# top_overview.net
KiCad netlist of a schematic drawn in Altium Designer
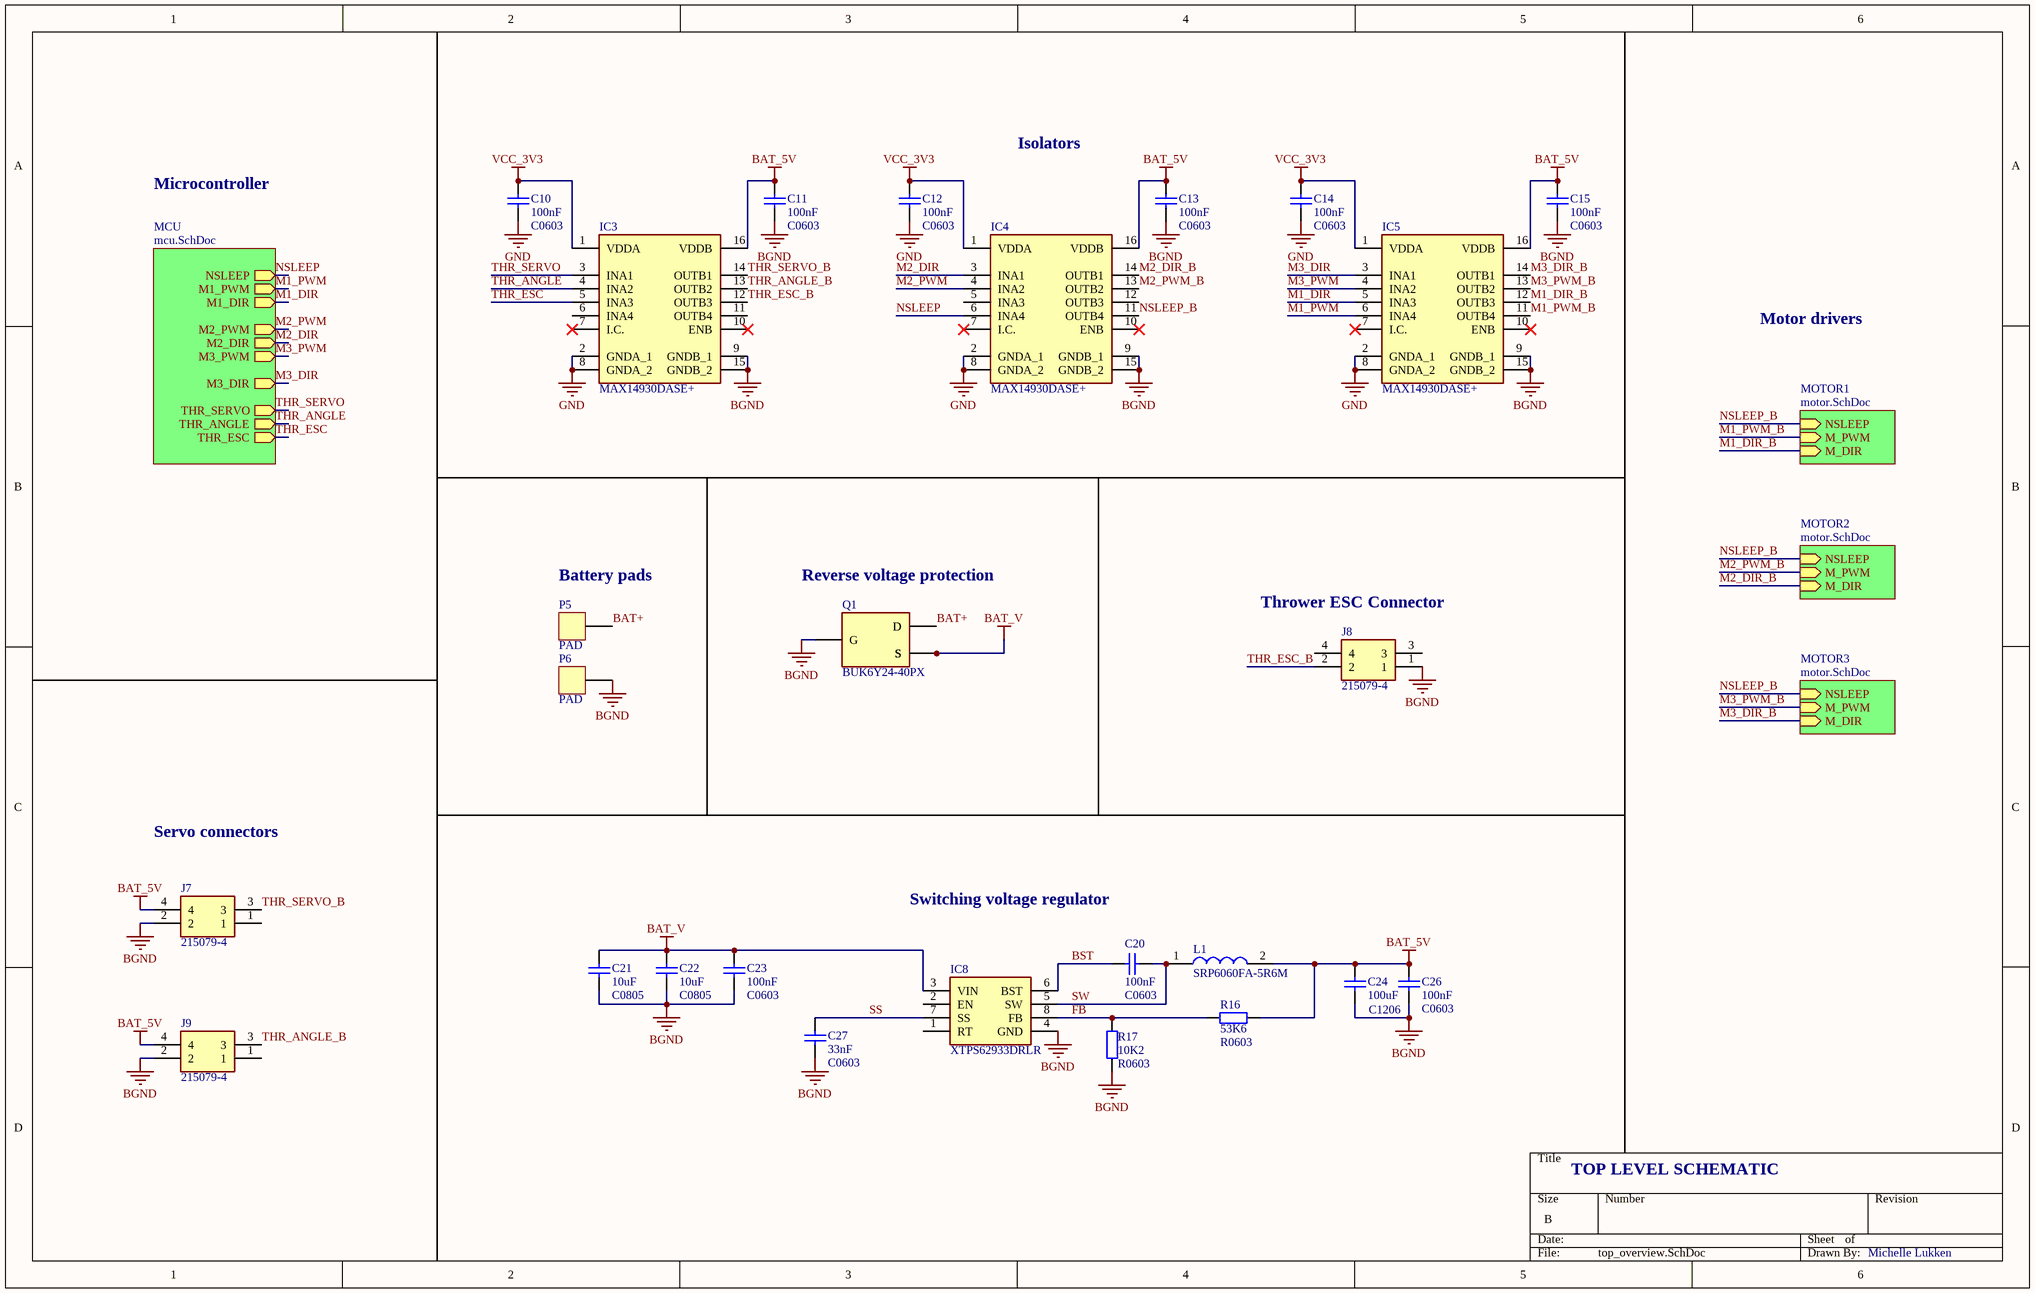
[diagram p0: top_overview.SchDoc]

(export (version "E")
  (design (tool "Eeschema 10.0.6"))
  (components
    (comp (ref "C10")
      (value "100nF*V")
      (footprint "PCB Passives:C0603")
      (description "Ceramic capacitor")
      (fields (field (name "CAPACITANCE") "100nF"))
      (libsource (lib "DeltaX_basketball_mikro") (part "Capacitor"))
    )
    (comp (ref "C11")
      (value "100nF*V")
      (footprint "PCB Passives:C0603")
      (description "Ceramic capacitor")
      (fields (field (name "CAPACITANCE") "100nF"))
      (libsource (lib "DeltaX_basketball_mikro") (part "Capacitor"))
    )
    (comp (ref "C12")
      (value "100nF*V")
      (footprint "PCB Passives:C0603")
      (description "Ceramic capacitor")
      (fields (field (name "CAPACITANCE") "100nF"))
      (libsource (lib "DeltaX_basketball_mikro") (part "Capacitor"))
    )
    (comp (ref "C13")
      (value "100nF*V")
      (footprint "PCB Passives:C0603")
      (description "Ceramic capacitor")
      (fields (field (name "CAPACITANCE") "100nF"))
      (libsource (lib "DeltaX_basketball_mikro") (part "Capacitor"))
    )
    (comp (ref "C14")
      (value "100nF*V")
      (footprint "PCB Passives:C0603")
      (description "Ceramic capacitor")
      (fields (field (name "CAPACITANCE") "100nF"))
      (libsource (lib "DeltaX_basketball_mikro") (part "Capacitor"))
    )
    (comp (ref "C15")
      (value "100nF*V")
      (footprint "PCB Passives:C0603")
      (description "Ceramic capacitor")
      (fields (field (name "CAPACITANCE") "100nF"))
      (libsource (lib "DeltaX_basketball_mikro") (part "Capacitor"))
    )
    (comp (ref "C20")
      (value "100nF*V")
      (footprint "PCB Passives:C0603")
      (description "Ceramic capacitor")
      (fields (field (name "CAPACITANCE") "100nF"))
      (libsource (lib "DeltaX_basketball_mikro") (part "Capacitor"))
    )
    (comp (ref "C21")
      (value "10uF*V")
      (footprint "C0805")
      (description "Ceramic capacitor")
      (fields (field (name "CAPACITANCE") "10uF"))
      (libsource (lib "DeltaX_basketball_mikro") (part "Capacitor"))
    )
    (comp (ref "C22")
      (value "10uF*V")
      (footprint "C0805")
      (description "Ceramic capacitor")
      (fields (field (name "CAPACITANCE") "10uF"))
      (libsource (lib "DeltaX_basketball_mikro") (part "Capacitor"))
    )
    (comp (ref "C23")
      (value "100nF*V")
      (footprint "PCB Passives:C0603")
      (description "Ceramic capacitor")
      (fields (field (name "CAPACITANCE") "100nF"))
      (libsource (lib "DeltaX_basketball_mikro") (part "Capacitor"))
    )
    (comp (ref "C24")
      (value "100uF*V")
      (footprint "C1206")
      (description "Ceramic capacitor")
      (fields (field (name "CAPACITANCE") "100uF"))
      (libsource (lib "DeltaX_basketball_mikro") (part "Capacitor"))
    )
    (comp (ref "C26")
      (value "100nF*V")
      (footprint "PCB Passives:C0603")
      (description "Ceramic capacitor")
      (fields (field (name "CAPACITANCE") "100nF"))
      (libsource (lib "DeltaX_basketball_mikro") (part "Capacitor"))
    )
    (comp (ref "C27")
      (value "33nF*V")
      (footprint "PCB Passives:C0603")
      (description "Ceramic capacitor")
      (fields (field (name "CAPACITANCE") "33nF"))
      (libsource (lib "DeltaX_basketball_mikro") (part "Capacitor"))
    )
    (comp (ref "IC3")
      (value "MAX14930DASE+")
      (footprint "SamacSys:SOIC127P600X175-16N")
      (description "Integrated Circuit")
      (fields
        (field (name "MANUFACTURER_PART_NUMBER") "MAX14930EASE+")
        (field (name "MOUSER PART NUMBER") "700-MAX14930EASE+")
      )
      (libsource (lib "DeltaX_basketball_mikro") (part "MAX14930DASE+"))
    )
    (comp (ref "IC4")
      (value "MAX14930DASE+")
      (footprint "SamacSys:SOIC127P600X175-16N")
      (description "Integrated Circuit")
      (fields
        (field (name "MANUFACTURER_PART_NUMBER") "MAX14930EASE+")
        (field (name "MOUSER PART NUMBER") "700-MAX14930EASE+")
      )
      (libsource (lib "DeltaX_basketball_mikro") (part "MAX14930DASE+"))
    )
    (comp (ref "IC5")
      (value "MAX14930DASE+")
      (footprint "SamacSys:SOIC127P600X175-16N")
      (description "Integrated Circuit")
      (fields
        (field (name "MANUFACTURER_PART_NUMBER") "MAX14930EASE+")
        (field (name "MOUSER PART NUMBER") "700-MAX14930EASE+")
      )
      (libsource (lib "DeltaX_basketball_mikro") (part "MAX14930DASE+"))
    )
    (comp (ref "IC8")
      (value "XTPS62933DRLR")
      (footprint "SamacSys:SOTFL50P160X60-8N")
      (description "Integrated Circuit")
      (fields
        (field (name "MANUFACTURER_PART_NUMBER") "TPS62933DRLR")
        (field (name "MOUSER PART NUMBER") "595-TPS62933DRLR")
      )
      (libsource (lib "DeltaX_basketball_mikro") (part "XTPS62933DRLR"))
    )
    (comp (ref "J7")
      (value "215079-4")
      (footprint "SamacSys:2150794")
      (description "Connector")
      (fields (field (name "MOUSER PART NUMBER") "571-215079-4"))
      (libsource (lib "DeltaX_basketball_mikro") (part "215079-4"))
    )
    (comp (ref "J8")
      (value "215079-4")
      (footprint "SamacSys:2150794")
      (description "Connector")
      (fields (field (name "MOUSER PART NUMBER") "571-215079-4"))
      (libsource (lib "DeltaX_basketball_mikro") (part "215079-4"))
    )
    (comp (ref "J9")
      (value "215079-4")
      (footprint "SamacSys:2150794")
      (description "Connector")
      (fields (field (name "MOUSER PART NUMBER") "571-215079-4"))
      (libsource (lib "DeltaX_basketball_mikro") (part "215079-4"))
    )
    (comp (ref "L1")
      (value "SRP6060FA-5R6M")
      (footprint "SamacSys:SRP6060FA5R6M")
      (description "Inductor")
      (fields (field (name "MOUSER PART NUMBER") "652-SRP6060FA-5R6M"))
      (libsource (lib "*") (part "SRP6060FA-5R6M"))
    )
    (comp (ref "P5") (value "PAD") (footprint "SamacSys:BIG_PAD") (libsource (lib "SamacSys") (part "PAD")))
    (comp (ref "P6") (value "PAD") (footprint "SamacSys:BIG_PAD") (libsource (lib "SamacSys") (part "PAD")))
    (comp (ref "Q1")
      (value "BUK6Y24-40PX")
      (footprint "SamacSys:BUK6Y2440PX")
      (description "MOSFET (P-Channel)")
      (fields (field (name "MOUSER PART NUMBER") "771-BUK6Y24-40PX"))
      (libsource (lib "DeltaX_basketball_mikro") (part "BUK6Y24-40PX"))
    )
    (comp (ref "R16")
      (value "53K6")
      (footprint "R0603")
      (description "Resistor")
      (fields (field (name "RESISTANCE") "53K6"))
      (libsource (lib "Component Library INTLIB") (part "Resistor"))
    )
    (comp (ref "R17")
      (value "10K2")
      (footprint "R0603")
      (description "Resistor")
      (fields (field (name "RESISTANCE") "10K2"))
      (libsource (lib "") (part "Resistor_1"))
    )
  )
  (nets
    (net (code "1") (name "/BAT+") (class "Default")
      (node (ref "P5") (pin "1") (pinfunction "PAD_1") (pintype "passive"))
      (node (ref "Q1") (pin "5") (pinfunction "D_5") (pintype "passive"))
      (node (ref "Q1") (pin "6") (pinfunction "D_6") (pintype "passive"))
    )
    (net (code "2") (name "/BST") (class "Default")
      (node (ref "C20") (pin "2") (pinfunction "2_2") (pintype "passive"))
      (node (ref "IC8") (pin "6") (pinfunction "BST_6") (pintype "passive"))
    )
    (net (code "3") (name "/FB") (class "Default")
      (node (ref "IC8") (pin "8") (pinfunction "FB_8") (pintype "passive"))
      (node (ref "R16") (pin "1") (pinfunction "1_1") (pintype "passive"))
      (node (ref "R17") (pin "1") (pinfunction "1_1") (pintype "passive"))
    )
    (net (code "4") (name "/M1_DIR") (class "Default")
      (node (ref "IC5") (pin "5") (pinfunction "INA3_5") (pintype "passive"))
    )
    (net (code "5") (name "/M1_DIR_B") (class "Default")
      (node (ref "IC5") (pin "12") (pinfunction "OUTB3_12") (pintype "passive"))
    )
    (net (code "6") (name "/M1_PWM") (class "Default")
      (node (ref "IC5") (pin "6") (pinfunction "INA4_6") (pintype "passive"))
    )
    (net (code "7") (name "/M1_PWM_B") (class "Default")
      (node (ref "IC5") (pin "11") (pinfunction "OUTB4_11") (pintype "passive"))
    )
    (net (code "8") (name "/M2_DIR") (class "Default")
      (node (ref "IC4") (pin "3") (pinfunction "INA1_3") (pintype "passive"))
    )
    (net (code "9") (name "/M2_DIR_B") (class "Default")
      (node (ref "IC4") (pin "14") (pinfunction "OUTB1_14") (pintype "passive"))
    )
    (net (code "10") (name "/M2_PWM") (class "Default")
      (node (ref "IC4") (pin "4") (pinfunction "INA2_4") (pintype "passive"))
    )
    (net (code "11") (name "/M2_PWM_B") (class "Default")
      (node (ref "IC4") (pin "13") (pinfunction "OUTB2_13") (pintype "passive"))
    )
    (net (code "12") (name "/M3_DIR") (class "Default")
      (node (ref "IC5") (pin "3") (pinfunction "INA1_3") (pintype "passive"))
    )
    (net (code "13") (name "/M3_DIR_B") (class "Default")
      (node (ref "IC5") (pin "14") (pinfunction "OUTB1_14") (pintype "passive"))
    )
    (net (code "14") (name "/M3_PWM") (class "Default")
      (node (ref "IC5") (pin "4") (pinfunction "INA2_4") (pintype "passive"))
    )
    (net (code "15") (name "/M3_PWM_B") (class "Default")
      (node (ref "IC5") (pin "13") (pinfunction "OUTB2_13") (pintype "passive"))
    )
    (net (code "16") (name "/NSLEEP") (class "Default")
      (node (ref "IC4") (pin "6") (pinfunction "INA4_6") (pintype "passive"))
    )
    (net (code "17") (name "/NSLEEP_B") (class "Default")
      (node (ref "IC4") (pin "11") (pinfunction "OUTB4_11") (pintype "passive"))
    )
    (net (code "18") (name "/SS") (class "Default")
      (node (ref "C27") (pin "2") (pinfunction "2_2") (pintype "passive"))
      (node (ref "IC8") (pin "7") (pinfunction "SS_7") (pintype "passive"))
    )
    (net (code "19") (name "/SW") (class "Default")
      (node (ref "C20") (pin "1") (pinfunction "1_1") (pintype "passive"))
      (node (ref "IC8") (pin "5") (pinfunction "SW_5") (pintype "passive"))
      (node (ref "L1") (pin "1") (pinfunction "1_1") (pintype "passive"))
    )
    (net (code "20") (name "/THR_ANGLE") (class "Default")
      (node (ref "IC3") (pin "4") (pinfunction "INA2_4") (pintype "passive"))
    )
    (net (code "21") (name "/THR_ANGLE_B") (class "Default")
      (node (ref "IC3") (pin "13") (pinfunction "OUTB2_13") (pintype "passive"))
      (node (ref "J9") (pin "3") (pinfunction "3_3") (pintype "passive"))
    )
    (net (code "22") (name "/THR_ESC") (class "Default")
      (node (ref "IC3") (pin "5") (pinfunction "INA3_5") (pintype "passive"))
    )
    (net (code "23") (name "/THR_ESC_B") (class "Default")
      (node (ref "IC3") (pin "12") (pinfunction "OUTB3_12") (pintype "passive"))
      (node (ref "J8") (pin "2") (pinfunction "2_2") (pintype "passive"))
    )
    (net (code "24") (name "/THR_SERVO") (class "Default")
      (node (ref "IC3") (pin "3") (pinfunction "INA1_3") (pintype "passive"))
    )
    (net (code "25") (name "/THR_SERVO_B") (class "Default")
      (node (ref "IC3") (pin "14") (pinfunction "OUTB1_14") (pintype "passive"))
      (node (ref "J7") (pin "3") (pinfunction "3_3") (pintype "passive"))
    )
    (net (code "26") (name "BAT_5V") (class "Default")
      (node (ref "C11") (pin "2") (pinfunction "2_2") (pintype "passive"))
      (node (ref "C13") (pin "2") (pinfunction "2_2") (pintype "passive"))
      (node (ref "C15") (pin "2") (pinfunction "2_2") (pintype "passive"))
      (node (ref "C24") (pin "1") (pinfunction "1_1") (pintype "passive"))
      (node (ref "C26") (pin "1") (pinfunction "1_1") (pintype "passive"))
      (node (ref "IC3") (pin "16") (pinfunction "VDDB_16") (pintype "passive"))
      (node (ref "IC4") (pin "16") (pinfunction "VDDB_16") (pintype "passive"))
      (node (ref "IC5") (pin "16") (pinfunction "VDDB_16") (pintype "passive"))
      (node (ref "J7") (pin "4") (pinfunction "4_4") (pintype "passive"))
      (node (ref "J9") (pin "4") (pinfunction "4_4") (pintype "passive"))
      (node (ref "L1") (pin "2") (pinfunction "2_2") (pintype "passive"))
      (node (ref "R16") (pin "2") (pinfunction "2_2") (pintype "passive"))
    )
    (net (code "27") (name "BAT_V") (class "Default")
      (node (ref "C21") (pin "2") (pinfunction "2_2") (pintype "passive"))
      (node (ref "C22") (pin "2") (pinfunction "2_2") (pintype "passive"))
      (node (ref "C23") (pin "2") (pinfunction "2_2") (pintype "passive"))
      (node (ref "IC8") (pin "3") (pinfunction "VIN_3") (pintype "passive"))
      (node (ref "Q1") (pin "1") (pinfunction "S_1") (pintype "passive"))
      (node (ref "Q1") (pin "2") (pinfunction "S_2") (pintype "passive"))
      (node (ref "Q1") (pin "3") (pinfunction "S_3") (pintype "passive"))
    )
    (net (code "28") (name "BGND") (class "Default")
      (node (ref "C11") (pin "1") (pinfunction "1_1") (pintype "passive"))
      (node (ref "C13") (pin "1") (pinfunction "1_1") (pintype "passive"))
      (node (ref "C15") (pin "1") (pinfunction "1_1") (pintype "passive"))
      (node (ref "C21") (pin "1") (pinfunction "1_1") (pintype "passive"))
      (node (ref "C22") (pin "1") (pinfunction "1_1") (pintype "passive"))
      (node (ref "C23") (pin "1") (pinfunction "1_1") (pintype "passive"))
      (node (ref "C24") (pin "2") (pinfunction "2_2") (pintype "passive"))
      (node (ref "C26") (pin "2") (pinfunction "2_2") (pintype "passive"))
      (node (ref "C27") (pin "1") (pinfunction "1_1") (pintype "passive"))
      (node (ref "IC3") (pin "15") (pinfunction "GNDB_2_15") (pintype "passive"))
      (node (ref "IC3") (pin "9") (pinfunction "GNDB_1_9") (pintype "passive"))
      (node (ref "IC4") (pin "15") (pinfunction "GNDB_2_15") (pintype "passive"))
      (node (ref "IC4") (pin "9") (pinfunction "GNDB_1_9") (pintype "passive"))
      (node (ref "IC5") (pin "15") (pinfunction "GNDB_2_15") (pintype "passive"))
      (node (ref "IC5") (pin "9") (pinfunction "GNDB_1_9") (pintype "passive"))
      (node (ref "IC8") (pin "4") (pinfunction "GND_4") (pintype "passive"))
      (node (ref "J7") (pin "2") (pinfunction "2_2") (pintype "passive"))
      (node (ref "J8") (pin "1") (pinfunction "1_1") (pintype "passive"))
      (node (ref "J9") (pin "2") (pinfunction "2_2") (pintype "passive"))
      (node (ref "P6") (pin "1") (pinfunction "PAD_1") (pintype "passive"))
      (node (ref "Q1") (pin "4") (pinfunction "G_4") (pintype "passive"))
      (node (ref "R17") (pin "2") (pinfunction "2_2") (pintype "passive"))
    )
    (net (code "29") (name "GND") (class "Default")
      (node (ref "C10") (pin "1") (pinfunction "1_1") (pintype "passive"))
      (node (ref "C12") (pin "1") (pinfunction "1_1") (pintype "passive"))
      (node (ref "C14") (pin "1") (pinfunction "1_1") (pintype "passive"))
      (node (ref "IC3") (pin "2") (pinfunction "GNDA_1_2") (pintype "passive"))
      (node (ref "IC3") (pin "8") (pinfunction "GNDA_2_8") (pintype "passive"))
      (node (ref "IC4") (pin "2") (pinfunction "GNDA_1_2") (pintype "passive"))
      (node (ref "IC4") (pin "8") (pinfunction "GNDA_2_8") (pintype "passive"))
      (node (ref "IC5") (pin "2") (pinfunction "GNDA_1_2") (pintype "passive"))
      (node (ref "IC5") (pin "8") (pinfunction "GNDA_2_8") (pintype "passive"))
    )
    (net (code "30") (name "VCC_3V3") (class "Default")
      (node (ref "C10") (pin "2") (pinfunction "2_2") (pintype "passive"))
      (node (ref "C12") (pin "2") (pinfunction "2_2") (pintype "passive"))
      (node (ref "C14") (pin "2") (pinfunction "2_2") (pintype "passive"))
      (node (ref "IC3") (pin "1") (pinfunction "VDDA_1") (pintype "passive"))
      (node (ref "IC4") (pin "1") (pinfunction "VDDA_1") (pintype "passive"))
      (node (ref "IC5") (pin "1") (pinfunction "VDDA_1") (pintype "passive"))
    )
    (net (code "31") (name "unconnected-(IC3-ENB-Pad10)") (class "Default")
      (node (ref "IC3") (pin "10") (pinfunction "ENB_10") (pintype "passive+no_connect"))
    )
    (net (code "32") (name "unconnected-(IC3-I.C.-Pad7)") (class "Default")
      (node (ref "IC3") (pin "7") (pinfunction "I.C._7") (pintype "passive+no_connect"))
    )
    (net (code "33") (name "unconnected-(IC3-INA4-Pad6)") (class "Default")
      (node (ref "IC3") (pin "6") (pinfunction "INA4_6") (pintype "passive"))
    )
    (net (code "34") (name "unconnected-(IC3-OUTB4-Pad11)") (class "Default")
      (node (ref "IC3") (pin "11") (pinfunction "OUTB4_11") (pintype "passive"))
    )
    (net (code "35") (name "unconnected-(IC4-ENB-Pad10)") (class "Default")
      (node (ref "IC4") (pin "10") (pinfunction "ENB_10") (pintype "passive+no_connect"))
    )
    (net (code "36") (name "unconnected-(IC4-I.C.-Pad7)") (class "Default")
      (node (ref "IC4") (pin "7") (pinfunction "I.C._7") (pintype "passive+no_connect"))
    )
    (net (code "37") (name "unconnected-(IC4-INA3-Pad5)") (class "Default")
      (node (ref "IC4") (pin "5") (pinfunction "INA3_5") (pintype "passive"))
    )
    (net (code "38") (name "unconnected-(IC4-OUTB3-Pad12)") (class "Default")
      (node (ref "IC4") (pin "12") (pinfunction "OUTB3_12") (pintype "passive"))
    )
    (net (code "39") (name "unconnected-(IC5-ENB-Pad10)") (class "Default")
      (node (ref "IC5") (pin "10") (pinfunction "ENB_10") (pintype "passive+no_connect"))
    )
    (net (code "40") (name "unconnected-(IC5-I.C.-Pad7)") (class "Default")
      (node (ref "IC5") (pin "7") (pinfunction "I.C._7") (pintype "passive+no_connect"))
    )
    (net (code "41") (name "unconnected-(IC8-EN-Pad2)") (class "Default")
      (node (ref "IC8") (pin "2") (pinfunction "EN_2") (pintype "passive"))
    )
    (net (code "42") (name "unconnected-(IC8-RT-Pad1)") (class "Default")
      (node (ref "IC8") (pin "1") (pinfunction "RT_1") (pintype "passive"))
    )
    (net (code "43") (name "unconnected-(J7-Pad1)") (class "Default")
      (node (ref "J7") (pin "1") (pinfunction "1_1") (pintype "passive"))
    )
    (net (code "44") (name "unconnected-(J8-Pad3)") (class "Default")
      (node (ref "J8") (pin "3") (pinfunction "3_3") (pintype "passive"))
    )
    (net (code "45") (name "unconnected-(J8-Pad4)") (class "Default")
      (node (ref "J8") (pin "4") (pinfunction "4_4") (pintype "passive"))
    )
    (net (code "46") (name "unconnected-(J9-Pad1)") (class "Default")
      (node (ref "J9") (pin "1") (pinfunction "1_1") (pintype "passive"))
    )
  )
)
